# VentilationSystem.net
KiCad netlist of a schematic drawn in EAGLE
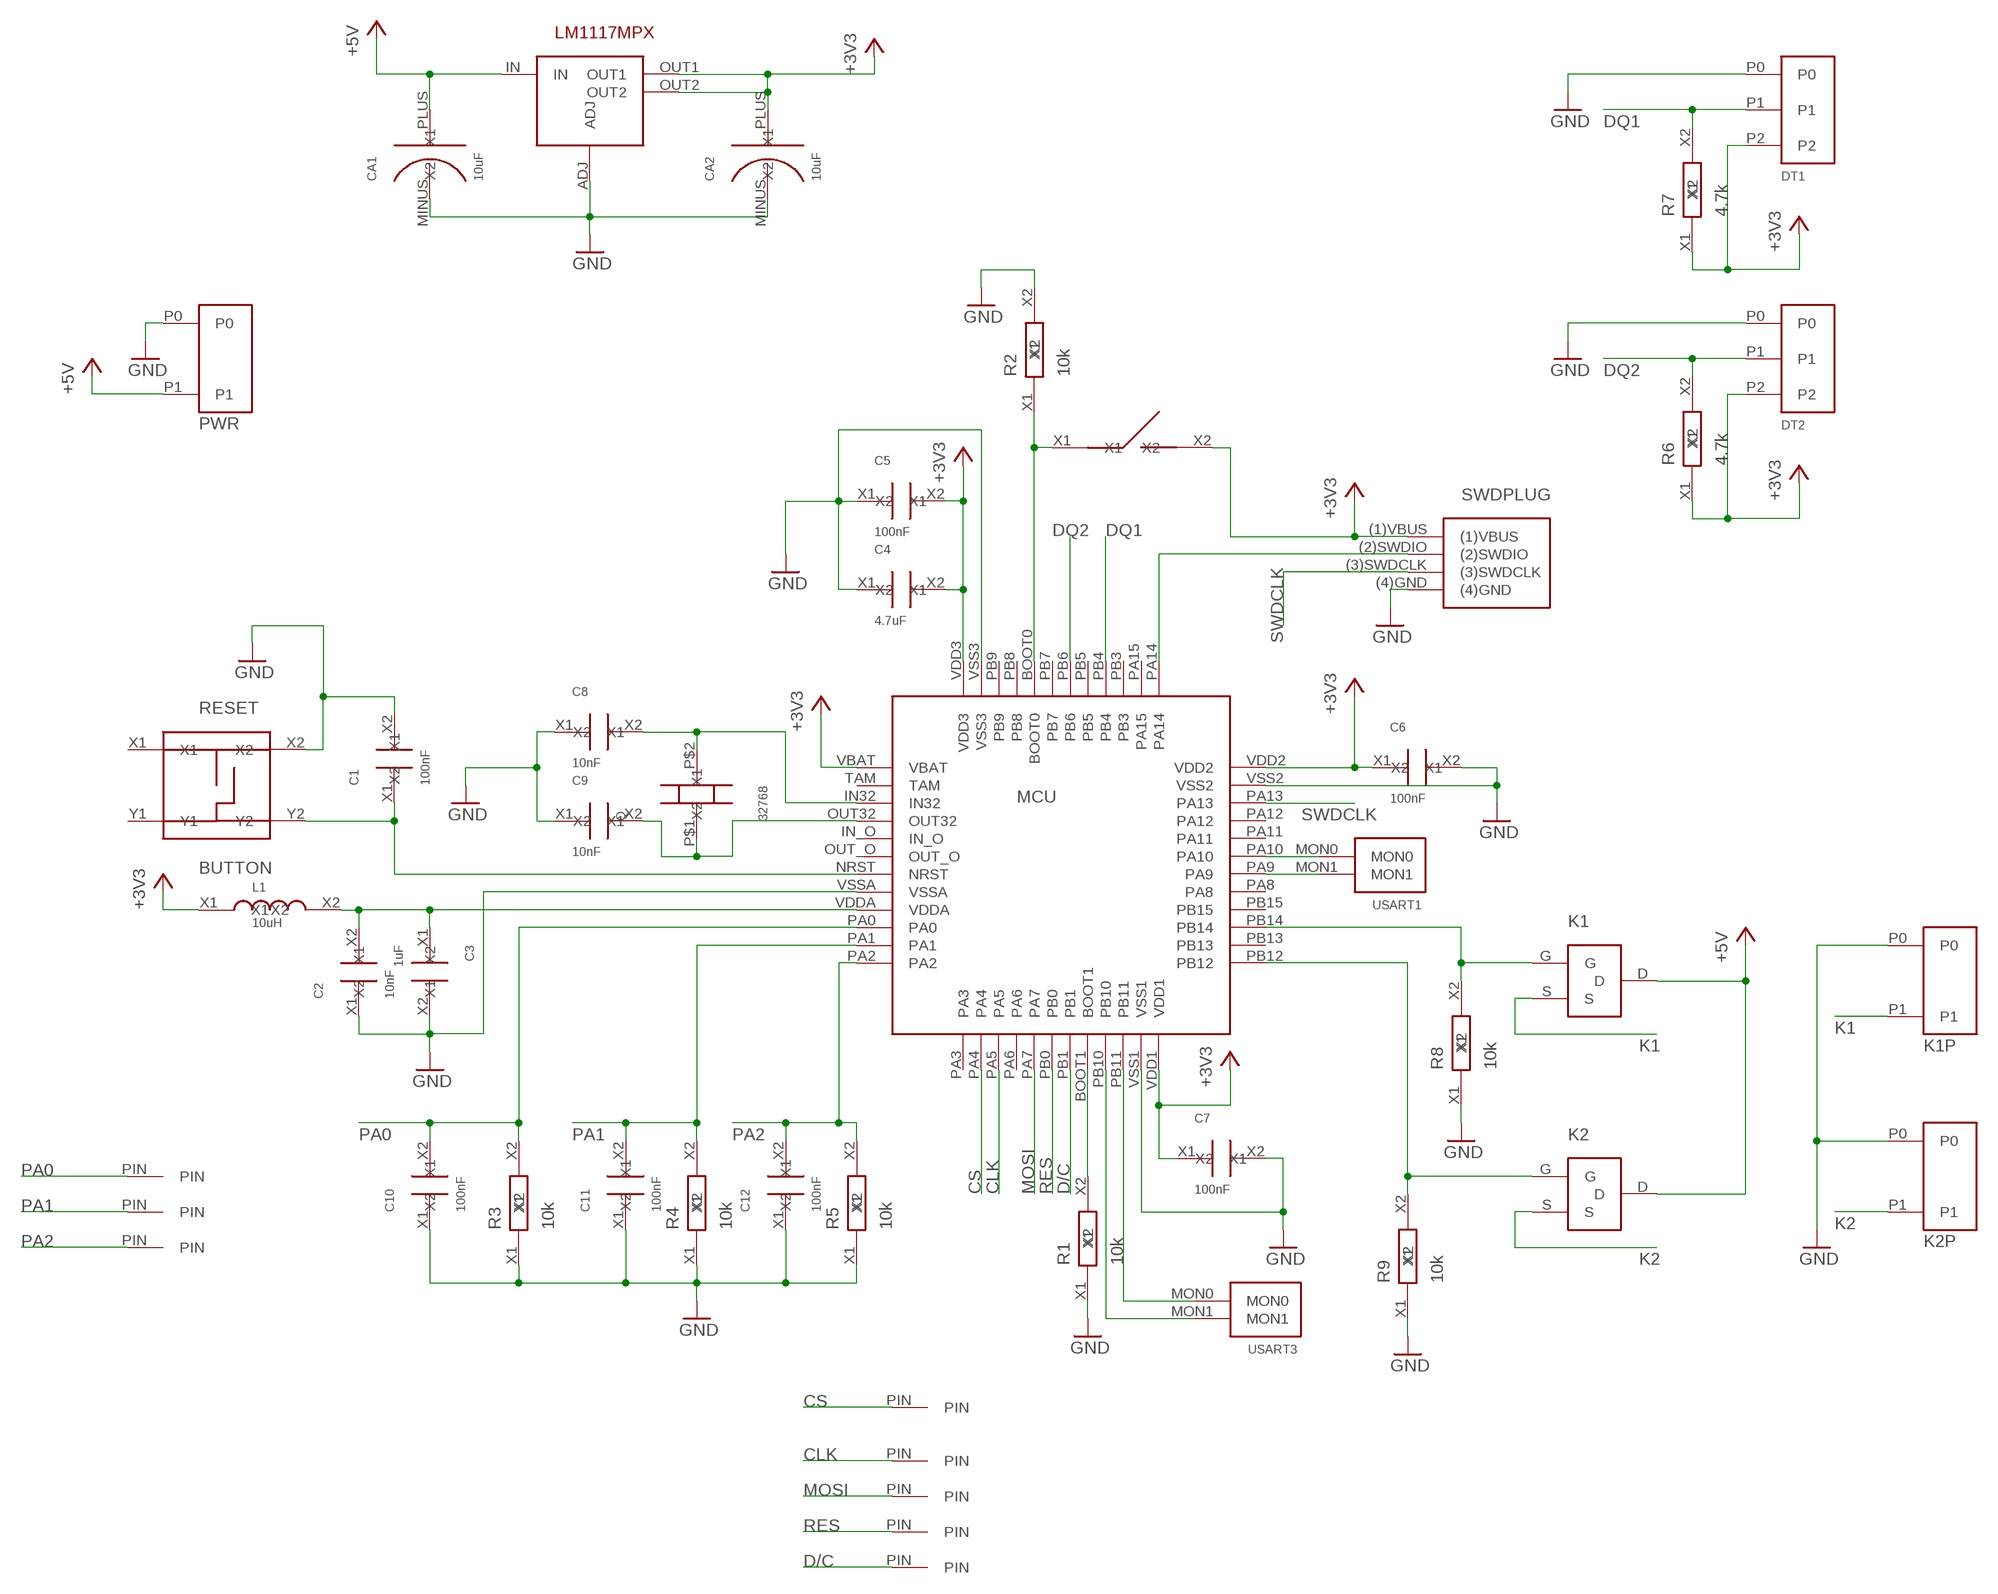
[diagram p0: schematic, sheet 1]

(export (version "E")
  (design (tool "Eeschema 10.0.6"))
  (components
    (comp (ref "C1")
      (value "100nF")
      (footprint "eagle-import:SMD_2.1X1.25")
      (libsource (lib "eagle-import") (part "C_SMD_2.1X1.25"))
    )
    (comp (ref "C2")
      (value "10nF")
      (footprint "eagle-import:SMD_2.1X1.25")
      (libsource (lib "eagle-import") (part "C_SMD_2.1X1.25"))
    )
    (comp (ref "C3")
      (value "1uF")
      (footprint "eagle-import:SMD_2.1X1.25")
      (libsource (lib "eagle-import") (part "C_SMD_2.1X1.25"))
    )
    (comp (ref "C4")
      (value "4.7uF")
      (footprint "eagle-import:SMD_2.1X1.25")
      (libsource (lib "eagle-import") (part "C_SMD_2.1X1.25"))
    )
    (comp (ref "C5")
      (value "100nF")
      (footprint "eagle-import:SMD_2.1X1.25")
      (libsource (lib "eagle-import") (part "C_SMD_2.1X1.25"))
    )
    (comp (ref "C6")
      (value "100nF")
      (footprint "eagle-import:SMD_2.1X1.25")
      (libsource (lib "eagle-import") (part "C_SMD_2.1X1.25"))
    )
    (comp (ref "C7")
      (value "100nF")
      (footprint "eagle-import:SMD_2.1X1.25")
      (libsource (lib "eagle-import") (part "C_SMD_2.1X1.25"))
    )
    (comp (ref "C8")
      (value "10nF")
      (footprint "eagle-import:SMD_2.1X1.25")
      (libsource (lib "eagle-import") (part "C_SMD_2.1X1.25"))
    )
    (comp (ref "C9")
      (value "10nF")
      (footprint "eagle-import:SMD_2.1X1.25")
      (libsource (lib "eagle-import") (part "C_SMD_2.1X1.25"))
    )
    (comp (ref "C10")
      (value "100nF")
      (footprint "eagle-import:SMD_2.1X1.25")
      (libsource (lib "eagle-import") (part "C_SMD_2.1X1.25"))
    )
    (comp (ref "C11")
      (value "100nF")
      (footprint "eagle-import:SMD_2.1X1.25")
      (libsource (lib "eagle-import") (part "C_SMD_2.1X1.25"))
    )
    (comp (ref "C12")
      (value "100nF")
      (footprint "eagle-import:SMD_2.1X1.25")
      (libsource (lib "eagle-import") (part "C_SMD_2.1X1.25"))
    )
    (comp (ref "CA1")
      (value "10uF")
      (footprint "eagle-import:C_SMD_TA_A")
      (libsource (lib "eagle-import") (part "C_SMD_TA_A"))
    )
    (comp (ref "CA2")
      (value "10uF")
      (footprint "eagle-import:C_SMD_TA_A")
      (libsource (lib "eagle-import") (part "C_SMD_TA_A"))
    )
    (comp (ref "CLKPIN")
      (value "PIN_1")
      (footprint "eagle-import:PIN_1")
      (libsource (lib "eagle-import") (part "PIN_1"))
    )
    (comp (ref "CSPIN")
      (value "PIN_1")
      (footprint "eagle-import:PIN_1")
      (libsource (lib "eagle-import") (part "PIN_1"))
    )
    (comp (ref "D/CPIN")
      (value "PIN_1")
      (footprint "eagle-import:PIN_1")
      (libsource (lib "eagle-import") (part "PIN_1"))
    )
    (comp (ref "DT1")
      (value "RAIL_3")
      (footprint "eagle-import:RAIL_3")
      (libsource (lib "eagle-import") (part "RAIL_3"))
    )
    (comp (ref "DT2")
      (value "RAIL_3")
      (footprint "eagle-import:RAIL_3")
      (libsource (lib "eagle-import") (part "RAIL_3"))
    )
    (comp (ref "K1")
      (value "IRFML8244TRPBF")
      (footprint "eagle-import:IRFML8244TRPBF")
      (libsource (lib "eagle-import") (part "IRFML8244TRPBF"))
    )
    (comp (ref "K1P")
      (value "RAIL_2")
      (footprint "eagle-import:RAIL_2")
      (libsource (lib "eagle-import") (part "RAIL_2"))
    )
    (comp (ref "K2")
      (value "IRFML8244TRPBF")
      (footprint "eagle-import:IRFML8244TRPBF")
      (libsource (lib "eagle-import") (part "IRFML8244TRPBF"))
    )
    (comp (ref "K2P")
      (value "RAIL_2")
      (footprint "eagle-import:RAIL_2")
      (libsource (lib "eagle-import") (part "RAIL_2"))
    )
    (comp (ref "L1")
      (value "10uH")
      (footprint "eagle-import:SMD_2.1X1.25")
      (libsource (lib "eagle-import") (part "L_SMD_2.1X1.25"))
    )
    (comp (ref "MCU")
      (value "STM32F103CBT6")
      (footprint "eagle-import:STM32F103CBT6")
      (libsource (lib "eagle-import") (part "STM32F103CBT6"))
    )
    (comp (ref "MOSIPIN")
      (value "PIN_1")
      (footprint "eagle-import:PIN_1")
      (libsource (lib "eagle-import") (part "PIN_1"))
    )
    (comp (ref "PA0PIN")
      (value "PIN_1")
      (footprint "eagle-import:PIN_1")
      (libsource (lib "eagle-import") (part "PIN_1"))
    )
    (comp (ref "PA1PIN")
      (value "PIN_1")
      (footprint "eagle-import:PIN_1")
      (libsource (lib "eagle-import") (part "PIN_1"))
    )
    (comp (ref "PA2PIN")
      (value "PIN_1")
      (footprint "eagle-import:PIN_1")
      (libsource (lib "eagle-import") (part "PIN_1"))
    )
    (comp (ref "PWR")
      (value "RAIL_2")
      (footprint "eagle-import:RAIL_2")
      (libsource (lib "eagle-import") (part "RAIL_2"))
    )
    (comp (ref "Q")
      (value "32768")
      (footprint "eagle-import:QUARTZ_CYL")
      (libsource (lib "eagle-import") (part "QUARTZ_CYL"))
    )
    (comp (ref "R1")
      (value "10k")
      (footprint "eagle-import:SMD_2.1X1.25")
      (libsource (lib "eagle-import") (part "R_SMD_2.1X1.25"))
    )
    (comp (ref "R2")
      (value "10k")
      (footprint "eagle-import:SMD_2.1X1.25")
      (libsource (lib "eagle-import") (part "R_SMD_2.1X1.25"))
    )
    (comp (ref "R3")
      (value "10k")
      (footprint "eagle-import:SMD_2.1X1.25")
      (libsource (lib "eagle-import") (part "R_SMD_2.1X1.25"))
    )
    (comp (ref "R4")
      (value "10k")
      (footprint "eagle-import:SMD_2.1X1.25")
      (libsource (lib "eagle-import") (part "R_SMD_2.1X1.25"))
    )
    (comp (ref "R5")
      (value "10k")
      (footprint "eagle-import:SMD_2.1X1.25")
      (libsource (lib "eagle-import") (part "R_SMD_2.1X1.25"))
    )
    (comp (ref "R6")
      (value "4.7k")
      (footprint "eagle-import:SMD_2.1X1.25")
      (libsource (lib "eagle-import") (part "R_SMD_2.1X1.25"))
    )
    (comp (ref "R7")
      (value "4.7k")
      (footprint "eagle-import:SMD_2.1X1.25")
      (libsource (lib "eagle-import") (part "R_SMD_2.1X1.25"))
    )
    (comp (ref "R8")
      (value "10k")
      (footprint "eagle-import:SMD_2.1X1.25")
      (libsource (lib "eagle-import") (part "R_SMD_2.1X1.25"))
    )
    (comp (ref "R9")
      (value "10k")
      (footprint "eagle-import:SMD_2.1X1.25")
      (libsource (lib "eagle-import") (part "R_SMD_2.1X1.25"))
    )
    (comp (ref "RESET")
      (value "BUTTON")
      (footprint "eagle-import:BUTTON")
      (libsource (lib "eagle-import") (part "BUTTON"))
    )
    (comp (ref "RESPIN")
      (value "PIN_1")
      (footprint "eagle-import:PIN_1")
      (libsource (lib "eagle-import") (part "PIN_1"))
    )
    (comp (ref "SWDPLUG")
      (value "SWD")
      (footprint "eagle-import:SWD")
      (libsource (lib "eagle-import") (part "SWD"))
    )
    (comp (ref "U$3")
      (value "DIP_1")
      (footprint "eagle-import:DIP_1")
      (libsource (lib "eagle-import") (part "DIP_1"))
    )
    (comp (ref "U$4")
      (value "LM1117MPX-ADJ")
      (footprint "eagle-import:LM1117MPX-ADJ")
      (libsource (lib "eagle-import") (part "LM1117MPX-ADJ"))
    )
    (comp (ref "USART1")
      (value "MON2PIN")
      (footprint "eagle-import:MON2PIN")
      (libsource (lib "eagle-import") (part "MON2PIN"))
    )
    (comp (ref "USART3")
      (value "MON2PIN")
      (footprint "eagle-import:MON2PIN")
      (libsource (lib "eagle-import") (part "MON2PIN"))
    )
  )
  (nets
    (net (code "1") (name "+3V3") (class "Default")
      (node (ref "C4") (pin "X2") (pinfunction "X2_X2") (pintype "bidirectional"))
      (node (ref "C5") (pin "X2") (pinfunction "X2_X2") (pintype "bidirectional"))
      (node (ref "C6") (pin "X1") (pinfunction "X1_X1") (pintype "bidirectional"))
      (node (ref "C7") (pin "X1") (pinfunction "X1_X1") (pintype "bidirectional"))
      (node (ref "CA2") (pin "PLUS") (pinfunction "X2_PLUS") (pintype "bidirectional"))
      (node (ref "DT1") (pin "P2") (pinfunction "P2_P2") (pintype "bidirectional"))
      (node (ref "DT2") (pin "P2") (pinfunction "P2_P2") (pintype "bidirectional"))
      (node (ref "L1") (pin "X1") (pinfunction "X1_X1") (pintype "bidirectional"))
      (node (ref "MCU") (pin "VBAT") (pinfunction "VBAT_VBAT") (pintype "bidirectional"))
      (node (ref "MCU") (pin "VDD1") (pinfunction "VDD1_VDD1") (pintype "bidirectional"))
      (node (ref "MCU") (pin "VDD2") (pinfunction "VDD2_VDD2") (pintype "bidirectional"))
      (node (ref "MCU") (pin "VDD3") (pinfunction "VDD3_VDD3") (pintype "bidirectional"))
      (node (ref "R6") (pin "X1") (pinfunction "X1_X1") (pintype "bidirectional"))
      (node (ref "R7") (pin "X1") (pinfunction "X1_X1") (pintype "bidirectional"))
      (node (ref "SWDPLUG") (pin "(1)VBUS") (pinfunction "(1)VBUS_(1)VBUS") (pintype "bidirectional"))
      (node (ref "U$3") (pin "X2") (pinfunction "X2_X2") (pintype "bidirectional"))
      (node (ref "U$4") (pin "OUT1") (pinfunction "OUT1_OUT1") (pintype "bidirectional"))
      (node (ref "U$4") (pin "OUT2") (pinfunction "OUT2_OUT2") (pintype "bidirectional"))
    )
    (net (code "2") (name "+5V") (class "Default")
      (node (ref "CA1") (pin "PLUS") (pinfunction "X2_PLUS") (pintype "bidirectional"))
      (node (ref "K1") (pin "D") (pinfunction "D_D") (pintype "bidirectional"))
      (node (ref "K2") (pin "D") (pinfunction "D_D") (pintype "bidirectional"))
      (node (ref "PWR") (pin "P1") (pinfunction "P1_P1") (pintype "bidirectional"))
      (node (ref "U$4") (pin "IN") (pinfunction "IN_IN") (pintype "bidirectional"))
    )
    (net (code "3") (name "/CLK") (class "Default")
      (node (ref "CLKPIN") (pin "PIN") (pinfunction "PIN_PIN") (pintype "bidirectional"))
      (node (ref "MCU") (pin "PA5") (pinfunction "PA5_PA5") (pintype "bidirectional"))
    )
    (net (code "4") (name "/CS") (class "Default")
      (node (ref "CSPIN") (pin "PIN") (pinfunction "PIN_PIN") (pintype "bidirectional"))
      (node (ref "MCU") (pin "PA4") (pinfunction "PA4_PA4") (pintype "bidirectional"))
    )
    (net (code "5") (name "/DQ1") (class "Default")
      (node (ref "DT1") (pin "P1") (pinfunction "P1_P1") (pintype "bidirectional"))
      (node (ref "MCU") (pin "PB4") (pinfunction "PB4_PB4") (pintype "bidirectional"))
      (node (ref "R7") (pin "X2") (pinfunction "X2_X2") (pintype "bidirectional"))
    )
    (net (code "6") (name "/DQ2") (class "Default")
      (node (ref "DT2") (pin "P1") (pinfunction "P1_P1") (pintype "bidirectional"))
      (node (ref "MCU") (pin "PB6") (pinfunction "PB6_PB6") (pintype "bidirectional"))
      (node (ref "R6") (pin "X2") (pinfunction "X2_X2") (pintype "bidirectional"))
    )
    (net (code "7") (name "/D{slash}C") (class "Default")
      (node (ref "D/CPIN") (pin "PIN") (pinfunction "PIN_PIN") (pintype "bidirectional"))
      (node (ref "MCU") (pin "PB1") (pinfunction "PB1_PB1") (pintype "bidirectional"))
    )
    (net (code "8") (name "/K1") (class "Default")
      (node (ref "K1") (pin "S") (pinfunction "S_S") (pintype "bidirectional"))
      (node (ref "K1P") (pin "P1") (pinfunction "P1_P1") (pintype "bidirectional"))
    )
    (net (code "9") (name "/K2") (class "Default")
      (node (ref "K2") (pin "S") (pinfunction "S_S") (pintype "bidirectional"))
      (node (ref "K2P") (pin "P1") (pinfunction "P1_P1") (pintype "bidirectional"))
    )
    (net (code "10") (name "/MOSI") (class "Default")
      (node (ref "MCU") (pin "PA7") (pinfunction "PA7_PA7") (pintype "bidirectional"))
      (node (ref "MOSIPIN") (pin "PIN") (pinfunction "PIN_PIN") (pintype "bidirectional"))
    )
    (net (code "11") (name "/PA0") (class "Default")
      (node (ref "C10") (pin "X2") (pinfunction "X2_X2") (pintype "bidirectional"))
      (node (ref "MCU") (pin "PA0") (pinfunction "PA0_PA0") (pintype "bidirectional"))
      (node (ref "PA0PIN") (pin "PIN") (pinfunction "PIN_PIN") (pintype "bidirectional"))
      (node (ref "R3") (pin "X2") (pinfunction "X2_X2") (pintype "bidirectional"))
    )
    (net (code "12") (name "/PA1") (class "Default")
      (node (ref "C11") (pin "X2") (pinfunction "X2_X2") (pintype "bidirectional"))
      (node (ref "MCU") (pin "PA1") (pinfunction "PA1_PA1") (pintype "bidirectional"))
      (node (ref "PA1PIN") (pin "PIN") (pinfunction "PIN_PIN") (pintype "bidirectional"))
      (node (ref "R4") (pin "X2") (pinfunction "X2_X2") (pintype "bidirectional"))
    )
    (net (code "13") (name "/PA2") (class "Default")
      (node (ref "C12") (pin "X2") (pinfunction "X2_X2") (pintype "bidirectional"))
      (node (ref "MCU") (pin "PA2") (pinfunction "PA2_PA2") (pintype "bidirectional"))
      (node (ref "PA2PIN") (pin "PIN") (pinfunction "PIN_PIN") (pintype "bidirectional"))
      (node (ref "R5") (pin "X2") (pinfunction "X2_X2") (pintype "bidirectional"))
    )
    (net (code "14") (name "/RES") (class "Default")
      (node (ref "MCU") (pin "PB0") (pinfunction "PB0_PB0") (pintype "bidirectional"))
      (node (ref "RESPIN") (pin "PIN") (pinfunction "PIN_PIN") (pintype "bidirectional"))
    )
    (net (code "15") (name "/SWDCLK") (class "Default")
      (node (ref "MCU") (pin "PA13") (pinfunction "PA13_PA13") (pintype "bidirectional"))
      (node (ref "SWDPLUG") (pin "(3)SWDCLK") (pinfunction "(3)SWDCLK_(3)SWDCLK") (pintype "bidirectional"))
    )
    (net (code "16") (name "GND") (class "Default")
      (node (ref "C1") (pin "X2") (pinfunction "X2_X2") (pintype "bidirectional"))
      (node (ref "C10") (pin "X1") (pinfunction "X1_X1") (pintype "bidirectional"))
      (node (ref "C11") (pin "X1") (pinfunction "X1_X1") (pintype "bidirectional"))
      (node (ref "C12") (pin "X1") (pinfunction "X1_X1") (pintype "bidirectional"))
      (node (ref "C2") (pin "X1") (pinfunction "X1_X1") (pintype "bidirectional"))
      (node (ref "C3") (pin "X2") (pinfunction "X2_X2") (pintype "bidirectional"))
      (node (ref "C4") (pin "X1") (pinfunction "X1_X1") (pintype "bidirectional"))
      (node (ref "C5") (pin "X1") (pinfunction "X1_X1") (pintype "bidirectional"))
      (node (ref "C6") (pin "X2") (pinfunction "X2_X2") (pintype "bidirectional"))
      (node (ref "C7") (pin "X2") (pinfunction "X2_X2") (pintype "bidirectional"))
      (node (ref "C8") (pin "X1") (pinfunction "X1_X1") (pintype "bidirectional"))
      (node (ref "C9") (pin "X1") (pinfunction "X1_X1") (pintype "bidirectional"))
      (node (ref "CA1") (pin "MINUS") (pinfunction "X1_MINUS") (pintype "bidirectional"))
      (node (ref "CA2") (pin "MINUS") (pinfunction "X1_MINUS") (pintype "bidirectional"))
      (node (ref "DT1") (pin "P0") (pinfunction "P0_P0") (pintype "bidirectional"))
      (node (ref "DT2") (pin "P0") (pinfunction "P0_P0") (pintype "bidirectional"))
      (node (ref "K1P") (pin "P0") (pinfunction "P0_P0") (pintype "bidirectional"))
      (node (ref "K2P") (pin "P0") (pinfunction "P0_P0") (pintype "bidirectional"))
      (node (ref "MCU") (pin "VSS1") (pinfunction "VSS1_VSS1") (pintype "bidirectional"))
      (node (ref "MCU") (pin "VSS2") (pinfunction "VSS2_VSS2") (pintype "bidirectional"))
      (node (ref "MCU") (pin "VSS3") (pinfunction "VSS3_VSS3") (pintype "bidirectional"))
      (node (ref "MCU") (pin "VSSA") (pinfunction "VSSA_VSSA") (pintype "bidirectional"))
      (node (ref "PWR") (pin "P0") (pinfunction "P0_P0") (pintype "bidirectional"))
      (node (ref "R1") (pin "X1") (pinfunction "X1_X1") (pintype "bidirectional"))
      (node (ref "R2") (pin "X2") (pinfunction "X2_X2") (pintype "bidirectional"))
      (node (ref "R3") (pin "X1") (pinfunction "X1_X1") (pintype "bidirectional"))
      (node (ref "R4") (pin "X1") (pinfunction "X1_X1") (pintype "bidirectional"))
      (node (ref "R5") (pin "X1") (pinfunction "X1_X1") (pintype "bidirectional"))
      (node (ref "R8") (pin "X1") (pinfunction "X1_X1") (pintype "bidirectional"))
      (node (ref "R9") (pin "X1") (pinfunction "X1_X1") (pintype "bidirectional"))
      (node (ref "RESET") (pin "X2") (pinfunction "X2_X2") (pintype "bidirectional"))
      (node (ref "SWDPLUG") (pin "(4)GND") (pinfunction "(4)GND_(4)GND") (pintype "bidirectional"))
      (node (ref "U$4") (pin "ADJ") (pinfunction "ADJ_ADJ") (pintype "bidirectional"))
    )
    (net (code "17") (name "Net-(C1-PadX1)") (class "Default")
      (node (ref "C1") (pin "X1") (pinfunction "X1_X1") (pintype "bidirectional"))
      (node (ref "MCU") (pin "NRST") (pinfunction "NRST_NRST") (pintype "bidirectional"))
      (node (ref "RESET") (pin "Y2") (pinfunction "Y2_Y2") (pintype "bidirectional"))
    )
    (net (code "18") (name "Net-(C2-PadX2)") (class "Default")
      (node (ref "C2") (pin "X2") (pinfunction "X2_X2") (pintype "bidirectional"))
      (node (ref "C3") (pin "X1") (pinfunction "X1_X1") (pintype "bidirectional"))
      (node (ref "L1") (pin "X2") (pinfunction "X2_X2") (pintype "bidirectional"))
      (node (ref "MCU") (pin "VDDA") (pinfunction "VDDA_VDDA") (pintype "bidirectional"))
    )
    (net (code "19") (name "Net-(K1-PadG)") (class "Default")
      (node (ref "K1") (pin "G") (pinfunction "G_G") (pintype "bidirectional"))
      (node (ref "MCU") (pin "PB14") (pinfunction "PB14_PB14") (pintype "bidirectional"))
      (node (ref "R8") (pin "X2") (pinfunction "X2_X2") (pintype "bidirectional"))
    )
    (net (code "20") (name "Net-(K2-PadG)") (class "Default")
      (node (ref "K2") (pin "G") (pinfunction "G_G") (pintype "bidirectional"))
      (node (ref "MCU") (pin "PB12") (pinfunction "PB12_PB12") (pintype "bidirectional"))
      (node (ref "R9") (pin "X2") (pinfunction "X2_X2") (pintype "bidirectional"))
    )
    (net (code "21") (name "Net-(MCU-PadBOOT0)") (class "Default")
      (node (ref "MCU") (pin "BOOT0") (pinfunction "BOOT0_BOOT0") (pintype "bidirectional"))
      (node (ref "R2") (pin "X1") (pinfunction "X1_X1") (pintype "bidirectional"))
      (node (ref "U$3") (pin "X1") (pinfunction "X1_X1") (pintype "bidirectional"))
    )
    (net (code "22") (name "Net-(MCU-PadBOOT1)") (class "Default")
      (node (ref "MCU") (pin "BOOT1") (pinfunction "BOOT1_BOOT1") (pintype "bidirectional"))
      (node (ref "R1") (pin "X2") (pinfunction "X2_X2") (pintype "bidirectional"))
    )
    (net (code "23") (name "Net-(MCU-PadPA9)") (class "Default")
      (node (ref "MCU") (pin "PA9") (pinfunction "PA9_PA9") (pintype "bidirectional"))
      (node (ref "USART1") (pin "MON1") (pinfunction "MON1_MON1") (pintype "bidirectional"))
    )
    (net (code "24") (name "Net-(MCU-PadPA10)") (class "Default")
      (node (ref "MCU") (pin "PA10") (pinfunction "PA10_PA10") (pintype "bidirectional"))
      (node (ref "USART1") (pin "MON0") (pinfunction "MON0_MON0") (pintype "bidirectional"))
    )
    (net (code "25") (name "Net-(MCU-PadPA14)") (class "Default")
      (node (ref "MCU") (pin "PA14") (pinfunction "PA14_PA14") (pintype "bidirectional"))
      (node (ref "SWDPLUG") (pin "(2)SWDIO") (pinfunction "(2)SWDIO_(2)SWDIO") (pintype "bidirectional"))
    )
    (net (code "26") (name "Net-(MCU-PadPB10)") (class "Default")
      (node (ref "MCU") (pin "PB10") (pinfunction "PB10_PB10") (pintype "bidirectional"))
      (node (ref "USART3") (pin "MON1") (pinfunction "MON1_MON1") (pintype "bidirectional"))
    )
    (net (code "27") (name "Net-(MCU-PadPB11)") (class "Default")
      (node (ref "MCU") (pin "PB11") (pinfunction "PB11_PB11") (pintype "bidirectional"))
      (node (ref "USART3") (pin "MON0") (pinfunction "MON0_MON0") (pintype "bidirectional"))
    )
    (net (code "28") (name "Net-(Q-X1)") (class "Default")
      (node (ref "C9") (pin "X2") (pinfunction "X2_X2") (pintype "bidirectional"))
      (node (ref "MCU") (pin "OUT32") (pinfunction "OUT32_OUT32") (pintype "bidirectional"))
      (node (ref "Q") (pin "P$1") (pinfunction "X1_P$1") (pintype "bidirectional"))
    )
    (net (code "29") (name "Net-(Q-X2)") (class "Default")
      (node (ref "C8") (pin "X2") (pinfunction "X2_X2") (pintype "bidirectional"))
      (node (ref "MCU") (pin "IN32") (pinfunction "IN32_IN32") (pintype "bidirectional"))
      (node (ref "Q") (pin "P$2") (pinfunction "X2_P$2") (pintype "bidirectional"))
    )
    (net (code "30") (name "unconnected-(MCU-PadIN_O)") (class "Default")
      (node (ref "MCU") (pin "IN_O") (pinfunction "IN_O_IN_O") (pintype "bidirectional"))
    )
    (net (code "31") (name "unconnected-(MCU-PadOUT_O)") (class "Default")
      (node (ref "MCU") (pin "OUT_O") (pinfunction "OUT_O_OUT_O") (pintype "bidirectional"))
    )
    (net (code "32") (name "unconnected-(MCU-PadPA3)") (class "Default")
      (node (ref "MCU") (pin "PA3") (pinfunction "PA3_PA3") (pintype "bidirectional"))
    )
    (net (code "33") (name "unconnected-(MCU-PadPA6)") (class "Default")
      (node (ref "MCU") (pin "PA6") (pinfunction "PA6_PA6") (pintype "bidirectional"))
    )
    (net (code "34") (name "unconnected-(MCU-PadPA8)") (class "Default")
      (node (ref "MCU") (pin "PA8") (pinfunction "PA8_PA8") (pintype "bidirectional"))
    )
    (net (code "35") (name "unconnected-(MCU-PadPA11)") (class "Default")
      (node (ref "MCU") (pin "PA11") (pinfunction "PA11_PA11") (pintype "bidirectional"))
    )
    (net (code "36") (name "unconnected-(MCU-PadPA12)") (class "Default")
      (node (ref "MCU") (pin "PA12") (pinfunction "PA12_PA12") (pintype "bidirectional"))
    )
    (net (code "37") (name "unconnected-(MCU-PadPA15)") (class "Default")
      (node (ref "MCU") (pin "PA15") (pinfunction "PA15_PA15") (pintype "bidirectional"))
    )
    (net (code "38") (name "unconnected-(MCU-PadPB3)") (class "Default")
      (node (ref "MCU") (pin "PB3") (pinfunction "PB3_PB3") (pintype "bidirectional"))
    )
    (net (code "39") (name "unconnected-(MCU-PadPB5)") (class "Default")
      (node (ref "MCU") (pin "PB5") (pinfunction "PB5_PB5") (pintype "bidirectional"))
    )
    (net (code "40") (name "unconnected-(MCU-PadPB7)") (class "Default")
      (node (ref "MCU") (pin "PB7") (pinfunction "PB7_PB7") (pintype "bidirectional"))
    )
    (net (code "41") (name "unconnected-(MCU-PadPB8)") (class "Default")
      (node (ref "MCU") (pin "PB8") (pinfunction "PB8_PB8") (pintype "bidirectional"))
    )
    (net (code "42") (name "unconnected-(MCU-PadPB9)") (class "Default")
      (node (ref "MCU") (pin "PB9") (pinfunction "PB9_PB9") (pintype "bidirectional"))
    )
    (net (code "43") (name "unconnected-(MCU-PadPB13)") (class "Default")
      (node (ref "MCU") (pin "PB13") (pinfunction "PB13_PB13") (pintype "bidirectional"))
    )
    (net (code "44") (name "unconnected-(MCU-PadPB15)") (class "Default")
      (node (ref "MCU") (pin "PB15") (pinfunction "PB15_PB15") (pintype "bidirectional"))
    )
    (net (code "45") (name "unconnected-(MCU-PadTAM)") (class "Default")
      (node (ref "MCU") (pin "TAM") (pinfunction "TAM_TAM") (pintype "bidirectional"))
    )
    (net (code "46") (name "unconnected-(RESET-PadX1)") (class "Default")
      (node (ref "RESET") (pin "X1") (pinfunction "X1_X1") (pintype "bidirectional"))
    )
    (net (code "47") (name "unconnected-(RESET-PadY1)") (class "Default")
      (node (ref "RESET") (pin "Y1") (pinfunction "Y1_Y1") (pintype "bidirectional"))
    )
  )
)
